# main_sheet.net
KiCad netlist of a schematic drawn in Altium Designer
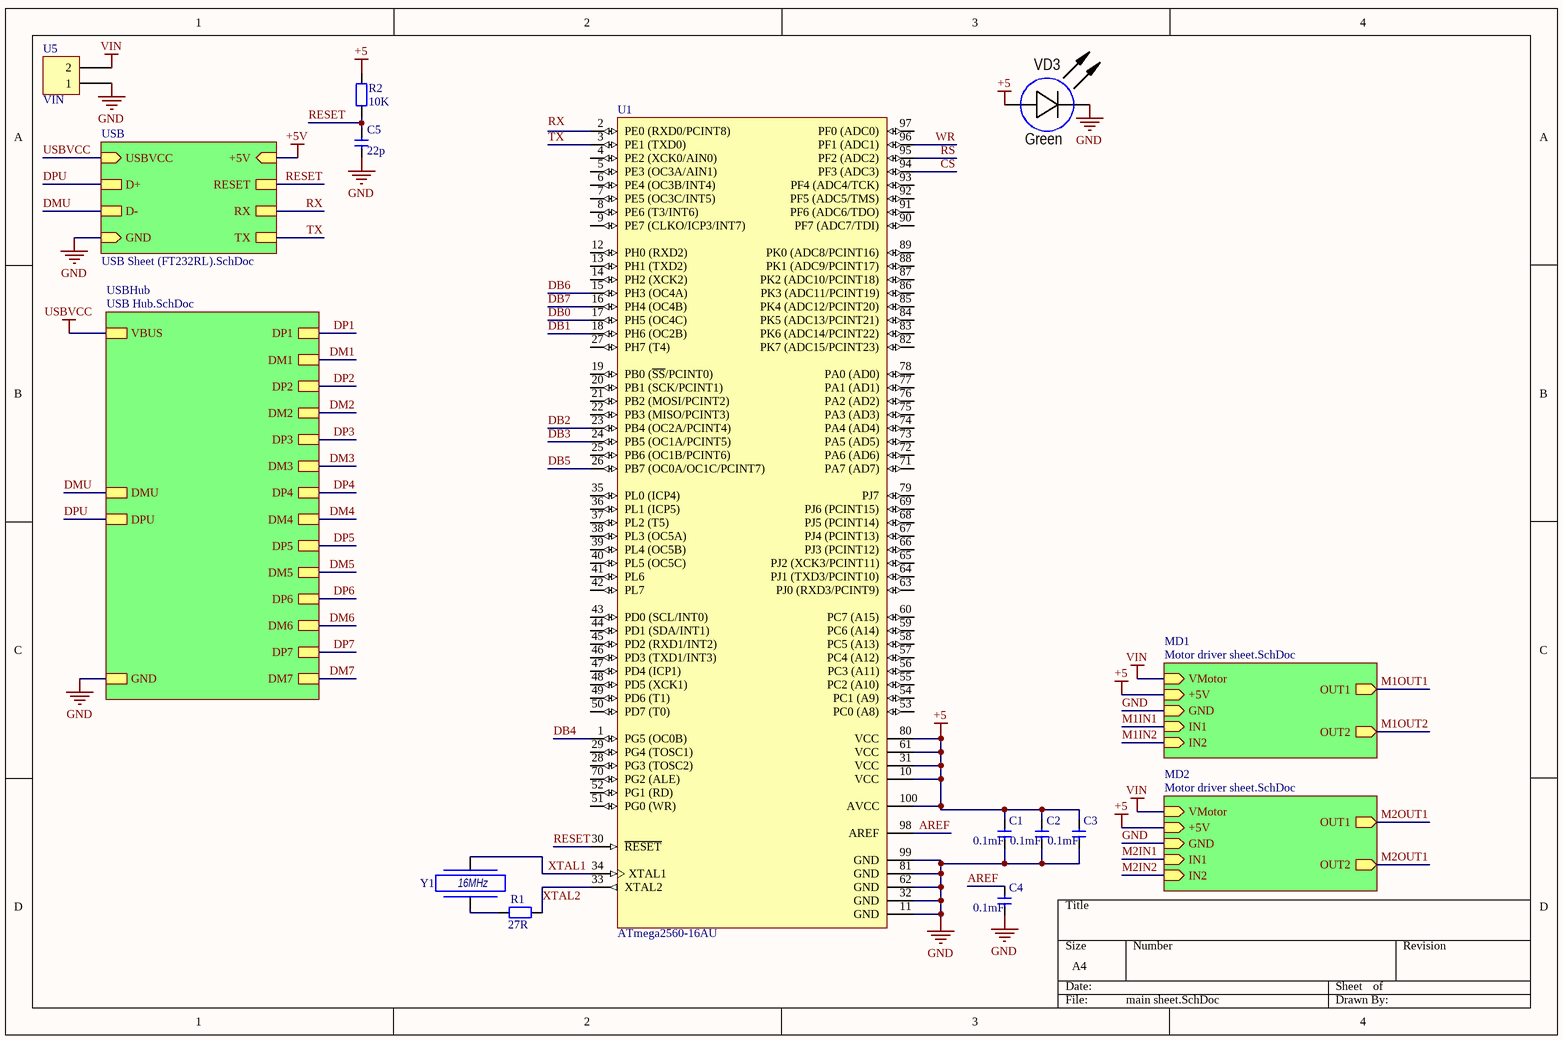
[diagram p0: main sheet.SchDoc]

(export (version "E")
  (design (tool "Eeschema 10.0.6"))
  (components
    (comp (ref "C1")
      (value "0.1mF")
      (footprint "cap0402")
      (libsource (lib "AlexChistiakov") (part "Cap SMD"))
    )
    (comp (ref "C2")
      (value "0.1mF")
      (footprint "cap0402")
      (libsource (lib "AlexChistiakov") (part "Cap SMD"))
    )
    (comp (ref "C3")
      (value "0.1mF")
      (footprint "cap0402")
      (libsource (lib "AlexChistiakov") (part "Cap SMD"))
    )
    (comp (ref "C4")
      (value "0.1mF")
      (footprint "cap0402")
      (libsource (lib "AlexChistiakov") (part "Cap SMD"))
    )
    (comp (ref "C5") (value "22p") (footprint "cap0603") (libsource (lib "AlexChistiakov") (part "Cap SMD")))
    (comp (ref "R1")
      (value "27R")
      (footprint "res0603")
      (libsource (lib "AlexChistiakov") (part "Resistor SMD"))
    )
    (comp (ref "R2")
      (value "10K")
      (footprint "res0603")
      (libsource (lib "AlexChistiakov") (part "Resistor SMD"))
    )
    (comp (ref "U1")
      (value "ATmega2560-16AU")
      (footprint "100A_N")
      (fields (field (name "PUBLISHER") "Altium Limited"))
      (libsource (lib "Atmel Microcontroller 8-Bit megaAVR") (part "ATmega2560-16AU"))
    )
    (comp (ref "U5")
      (value "VIN")
      (footprint "Power connectors")
      (libsource (lib "AlexChistiakov") (part "Power connectors"))
    )
    (comp (ref "VD3") (value "Green") (footprint "CH0603LB") (libsource (lib "Discrete") (part "LED")))
    (comp (ref "Y1")
      (value "16MHz")
      (footprint "QSMD5.0x3.2x1.0")
      (description "Кварцевый резонатор")
      (libsource (lib "TarabusLib_KOR") (part "Crystal"))
    )
  )
  (nets
    (net (code "1") (name "+5") (class "Default")
      (node (ref "C1") (pin "2") (pinfunction "2_2") (pintype "passive"))
      (node (ref "C2") (pin "2") (pinfunction "2_2") (pintype "passive"))
      (node (ref "C3") (pin "2") (pinfunction "2_2") (pintype "passive"))
      (node (ref "R2") (pin "2") (pinfunction "2_2") (pintype "passive"))
      (node (ref "U1") (pin "10") (pinfunction "VCC_10") (pintype "power_in"))
      (node (ref "U1") (pin "100") (pinfunction "AVCC_100") (pintype "power_in"))
      (node (ref "U1") (pin "31") (pinfunction "VCC_31") (pintype "power_in"))
      (node (ref "U1") (pin "61") (pinfunction "VCC_61") (pintype "power_in"))
      (node (ref "U1") (pin "80") (pinfunction "VCC_80") (pintype "power_in"))
      (node (ref "VD3") (pin "1") (pinfunction "A_1") (pintype "passive"))
    )
    (net (code "3") (name "/AREF") (class "Default")
      (node (ref "C4") (pin "2") (pinfunction "2_2") (pintype "passive"))
      (node (ref "U1") (pin "98") (pinfunction "AREF_98") (pintype "power_in"))
    )
    (net (code "4") (name "/CS") (class "Default")
      (node (ref "U1") (pin "94") (pinfunction "PF3_(ADC3)_94") (pintype "bidirectional"))
    )
    (net (code "5") (name "/DB0") (class "Default")
      (node (ref "U1") (pin "17") (pinfunction "PH5_(OC4C)_17") (pintype "bidirectional"))
    )
    (net (code "6") (name "/DB1") (class "Default")
      (node (ref "U1") (pin "18") (pinfunction "PH6_(OC2B)_18") (pintype "bidirectional"))
    )
    (net (code "7") (name "/DB2") (class "Default")
      (node (ref "U1") (pin "23") (pinfunction "PB4_(OC2A/PCINT4)_23") (pintype "bidirectional"))
    )
    (net (code "8") (name "/DB3") (class "Default")
      (node (ref "U1") (pin "24") (pinfunction "PB5_(OC1A/PCINT5)_24") (pintype "bidirectional"))
    )
    (net (code "9") (name "/DB4") (class "Default")
      (node (ref "U1") (pin "1") (pinfunction "PG5_(OC0B)_1") (pintype "bidirectional"))
    )
    (net (code "10") (name "/DB5") (class "Default")
      (node (ref "U1") (pin "26") (pinfunction "PB7_(OC0A/OC1C/PCINT7)_26") (pintype "bidirectional"))
    )
    (net (code "11") (name "/DB6") (class "Default")
      (node (ref "U1") (pin "15") (pinfunction "PH3_(OC4A)_15") (pintype "bidirectional"))
    )
    (net (code "12") (name "/DB7") (class "Default")
      (node (ref "U1") (pin "16") (pinfunction "PH4_(OC4B)_16") (pintype "bidirectional"))
    )
    (net (code "36") (name "/RESET") (class "Default")
      (node (ref "C5") (pin "2") (pinfunction "2_2") (pintype "passive"))
      (node (ref "R2") (pin "1") (pinfunction "1_1") (pintype "passive"))
      (node (ref "U1") (pin "30") (pinfunction "~{RESET}_30") (pintype "input"))
    )
    (net (code "37") (name "/RS") (class "Default")
      (node (ref "U1") (pin "95") (pinfunction "PF2_(ADC2)_95") (pintype "bidirectional"))
    )
    (net (code "39") (name "/TX") (class "Default")
      (node (ref "U1") (pin "3") (pinfunction "PE1_(TXD0)_3") (pintype "bidirectional"))
    )
    (net (code "40") (name "/WR") (class "Default")
      (node (ref "U1") (pin "96") (pinfunction "PF1_(ADC1)_96") (pintype "bidirectional"))
    )
    (net (code "41") (name "/XTAL1") (class "Default")
      (node (ref "U1") (pin "34") (pinfunction "XTAL1_34") (pintype "input"))
      (node (ref "Y1") (pin "2") (pinfunction "2_2") (pintype "passive"))
    )
    (net (code "42") (name "/XTAL2") (class "Default")
      (node (ref "R1") (pin "2") (pinfunction "2_2") (pintype "passive"))
      (node (ref "U1") (pin "33") (pinfunction "XTAL2_33") (pintype "output"))
    )
    (net (code "43") (name "GND") (class "Default")
      (node (ref "C1") (pin "1") (pinfunction "1_1") (pintype "passive"))
      (node (ref "C2") (pin "1") (pinfunction "1_1") (pintype "passive"))
      (node (ref "C3") (pin "1") (pinfunction "1_1") (pintype "passive"))
      (node (ref "C4") (pin "1") (pinfunction "1_1") (pintype "passive"))
      (node (ref "C5") (pin "1") (pinfunction "1_1") (pintype "passive"))
      (node (ref "U1") (pin "11") (pinfunction "GND_11") (pintype "power_in"))
      (node (ref "U1") (pin "32") (pinfunction "GND_32") (pintype "power_in"))
      (node (ref "U1") (pin "62") (pinfunction "GND_62") (pintype "power_in"))
      (node (ref "U1") (pin "81") (pinfunction "GND_81") (pintype "power_in"))
      (node (ref "U1") (pin "99") (pinfunction "GND_99") (pintype "power_in"))
      (node (ref "U5") (pin "1") (pinfunction "1_1") (pintype "power_in"))
      (node (ref "VD3") (pin "2") (pinfunction "C_2") (pintype "passive"))
    )
    (net (code "44") (name "Net-(R1-Pad1)") (class "Default")
      (node (ref "R1") (pin "1") (pinfunction "1_1") (pintype "passive"))
      (node (ref "Y1") (pin "1") (pinfunction "1_1") (pintype "passive"))
    )
    (net (code "46") (name "VIN") (class "Default")
      (node (ref "U5") (pin "2") (pinfunction "2_2") (pintype "power_in"))
    )
    (net (code "47") (name "unconnected-(U1-PA0_(AD0)-Pad78)") (class "Default")
      (node (ref "U1") (pin "78") (pinfunction "PA0_(AD0)_78") (pintype "bidirectional"))
    )
    (net (code "48") (name "unconnected-(U1-PA1_(AD1)-Pad77)") (class "Default")
      (node (ref "U1") (pin "77") (pinfunction "PA1_(AD1)_77") (pintype "bidirectional"))
    )
    (net (code "49") (name "unconnected-(U1-PA2_(AD2)-Pad76)") (class "Default")
      (node (ref "U1") (pin "76") (pinfunction "PA2_(AD2)_76") (pintype "bidirectional"))
    )
    (net (code "50") (name "unconnected-(U1-PA3_(AD3)-Pad75)") (class "Default")
      (node (ref "U1") (pin "75") (pinfunction "PA3_(AD3)_75") (pintype "bidirectional"))
    )
    (net (code "51") (name "unconnected-(U1-PA4_(AD4)-Pad74)") (class "Default")
      (node (ref "U1") (pin "74") (pinfunction "PA4_(AD4)_74") (pintype "bidirectional"))
    )
    (net (code "52") (name "unconnected-(U1-PA5_(AD5)-Pad73)") (class "Default")
      (node (ref "U1") (pin "73") (pinfunction "PA5_(AD5)_73") (pintype "bidirectional"))
    )
    (net (code "53") (name "unconnected-(U1-PA6_(AD6)-Pad72)") (class "Default")
      (node (ref "U1") (pin "72") (pinfunction "PA6_(AD6)_72") (pintype "bidirectional"))
    )
    (net (code "54") (name "unconnected-(U1-PA7_(AD7)-Pad71)") (class "Default")
      (node (ref "U1") (pin "71") (pinfunction "PA7_(AD7)_71") (pintype "bidirectional"))
    )
    (net (code "55") (name "unconnected-(U1-PB0_(~{SS}{slash}PCINT0)-Pad19)") (class "Default")
      (node (ref "U1") (pin "19") (pinfunction "PB0_(~{SS}/PCINT0)_19") (pintype "bidirectional"))
    )
    (net (code "56") (name "unconnected-(U1-PB1_(SCK{slash}PCINT1)-Pad20)") (class "Default")
      (node (ref "U1") (pin "20") (pinfunction "PB1_(SCK/PCINT1)_20") (pintype "bidirectional"))
    )
    (net (code "57") (name "unconnected-(U1-PB2_(MOSI{slash}PCINT2)-Pad21)") (class "Default")
      (node (ref "U1") (pin "21") (pinfunction "PB2_(MOSI/PCINT2)_21") (pintype "bidirectional"))
    )
    (net (code "58") (name "unconnected-(U1-PB3_(MISO{slash}PCINT3)-Pad22)") (class "Default")
      (node (ref "U1") (pin "22") (pinfunction "PB3_(MISO/PCINT3)_22") (pintype "bidirectional"))
    )
    (net (code "59") (name "unconnected-(U1-PB6_(OC1B{slash}PCINT6)-Pad25)") (class "Default")
      (node (ref "U1") (pin "25") (pinfunction "PB6_(OC1B/PCINT6)_25") (pintype "bidirectional"))
    )
    (net (code "60") (name "unconnected-(U1-PC0_(A8)-Pad53)") (class "Default")
      (node (ref "U1") (pin "53") (pinfunction "PC0_(A8)_53") (pintype "bidirectional"))
    )
    (net (code "61") (name "unconnected-(U1-PC1_(A9)-Pad54)") (class "Default")
      (node (ref "U1") (pin "54") (pinfunction "PC1_(A9)_54") (pintype "bidirectional"))
    )
    (net (code "62") (name "unconnected-(U1-PC2_(A10)-Pad55)") (class "Default")
      (node (ref "U1") (pin "55") (pinfunction "PC2_(A10)_55") (pintype "bidirectional"))
    )
    (net (code "63") (name "unconnected-(U1-PC3_(A11)-Pad56)") (class "Default")
      (node (ref "U1") (pin "56") (pinfunction "PC3_(A11)_56") (pintype "bidirectional"))
    )
    (net (code "64") (name "unconnected-(U1-PC4_(A12)-Pad57)") (class "Default")
      (node (ref "U1") (pin "57") (pinfunction "PC4_(A12)_57") (pintype "bidirectional"))
    )
    (net (code "65") (name "unconnected-(U1-PC5_(A13)-Pad58)") (class "Default")
      (node (ref "U1") (pin "58") (pinfunction "PC5_(A13)_58") (pintype "bidirectional"))
    )
    (net (code "66") (name "unconnected-(U1-PC6_(A14)-Pad59)") (class "Default")
      (node (ref "U1") (pin "59") (pinfunction "PC6_(A14)_59") (pintype "bidirectional"))
    )
    (net (code "67") (name "unconnected-(U1-PC7_(A15)-Pad60)") (class "Default")
      (node (ref "U1") (pin "60") (pinfunction "PC7_(A15)_60") (pintype "bidirectional"))
    )
    (net (code "68") (name "unconnected-(U1-PD0_(SCL{slash}INT0)-Pad43)") (class "Default")
      (node (ref "U1") (pin "43") (pinfunction "PD0_(SCL/INT0)_43") (pintype "bidirectional"))
    )
    (net (code "69") (name "unconnected-(U1-PD1_(SDA{slash}INT1)-Pad44)") (class "Default")
      (node (ref "U1") (pin "44") (pinfunction "PD1_(SDA/INT1)_44") (pintype "bidirectional"))
    )
    (net (code "70") (name "unconnected-(U1-PD2_(RXD1{slash}INT2)-Pad45)") (class "Default")
      (node (ref "U1") (pin "45") (pinfunction "PD2_(RXD1/INT2)_45") (pintype "bidirectional"))
    )
    (net (code "71") (name "unconnected-(U1-PD3_(TXD1{slash}INT3)-Pad46)") (class "Default")
      (node (ref "U1") (pin "46") (pinfunction "PD3_(TXD1/INT3)_46") (pintype "bidirectional"))
    )
    (net (code "72") (name "unconnected-(U1-PD4_(ICP1)-Pad47)") (class "Default")
      (node (ref "U1") (pin "47") (pinfunction "PD4_(ICP1)_47") (pintype "bidirectional"))
    )
    (net (code "73") (name "unconnected-(U1-PD5_(XCK1)-Pad48)") (class "Default")
      (node (ref "U1") (pin "48") (pinfunction "PD5_(XCK1)_48") (pintype "bidirectional"))
    )
    (net (code "74") (name "unconnected-(U1-PD6_(T1)-Pad49)") (class "Default")
      (node (ref "U1") (pin "49") (pinfunction "PD6_(T1)_49") (pintype "bidirectional"))
    )
    (net (code "75") (name "unconnected-(U1-PD7_(T0)-Pad50)") (class "Default")
      (node (ref "U1") (pin "50") (pinfunction "PD7_(T0)_50") (pintype "bidirectional"))
    )
    (net (code "76") (name "unconnected-(U1-PE0_(RXD0{slash}PCINT8)-Pad2)") (class "Default")
      (node (ref "U1") (pin "2") (pinfunction "PE0_(RXD0/PCINT8)_2") (pintype "bidirectional"))
    )
    (net (code "77") (name "unconnected-(U1-PE2_(XCK0{slash}AIN0)-Pad4)") (class "Default")
      (node (ref "U1") (pin "4") (pinfunction "PE2_(XCK0/AIN0)_4") (pintype "bidirectional"))
    )
    (net (code "78") (name "unconnected-(U1-PE3_(OC3A{slash}AIN1)-Pad5)") (class "Default")
      (node (ref "U1") (pin "5") (pinfunction "PE3_(OC3A/AIN1)_5") (pintype "bidirectional"))
    )
    (net (code "79") (name "unconnected-(U1-PE4_(OC3B{slash}INT4)-Pad6)") (class "Default")
      (node (ref "U1") (pin "6") (pinfunction "PE4_(OC3B/INT4)_6") (pintype "bidirectional"))
    )
    (net (code "80") (name "unconnected-(U1-PE5_(OC3C{slash}INT5)-Pad7)") (class "Default")
      (node (ref "U1") (pin "7") (pinfunction "PE5_(OC3C/INT5)_7") (pintype "bidirectional"))
    )
    (net (code "81") (name "unconnected-(U1-PE6_(T3{slash}INT6)-Pad8)") (class "Default")
      (node (ref "U1") (pin "8") (pinfunction "PE6_(T3/INT6)_8") (pintype "bidirectional"))
    )
    (net (code "82") (name "unconnected-(U1-PE7_(CLKO{slash}ICP3{slash}INT7)-Pad9)") (class "Default")
      (node (ref "U1") (pin "9") (pinfunction "PE7_(CLKO/ICP3/INT7)_9") (pintype "bidirectional"))
    )
    (net (code "83") (name "unconnected-(U1-PF0_(ADC0)-Pad97)") (class "Default")
      (node (ref "U1") (pin "97") (pinfunction "PF0_(ADC0)_97") (pintype "bidirectional"))
    )
    (net (code "84") (name "unconnected-(U1-PF4_(ADC4{slash}TCK)-Pad93)") (class "Default")
      (node (ref "U1") (pin "93") (pinfunction "PF4_(ADC4/TCK)_93") (pintype "bidirectional"))
    )
    (net (code "85") (name "unconnected-(U1-PF5_(ADC5{slash}TMS)-Pad92)") (class "Default")
      (node (ref "U1") (pin "92") (pinfunction "PF5_(ADC5/TMS)_92") (pintype "bidirectional"))
    )
    (net (code "86") (name "unconnected-(U1-PF6_(ADC6{slash}TDO)-Pad91)") (class "Default")
      (node (ref "U1") (pin "91") (pinfunction "PF6_(ADC6/TDO)_91") (pintype "bidirectional"))
    )
    (net (code "87") (name "unconnected-(U1-PF7_(ADC7{slash}TDI)-Pad90)") (class "Default")
      (node (ref "U1") (pin "90") (pinfunction "PF7_(ADC7/TDI)_90") (pintype "bidirectional"))
    )
    (net (code "88") (name "unconnected-(U1-PG0_(WR)-Pad51)") (class "Default")
      (node (ref "U1") (pin "51") (pinfunction "PG0_(WR)_51") (pintype "bidirectional"))
    )
    (net (code "89") (name "unconnected-(U1-PG1_(RD)-Pad52)") (class "Default")
      (node (ref "U1") (pin "52") (pinfunction "PG1_(RD)_52") (pintype "bidirectional"))
    )
    (net (code "90") (name "unconnected-(U1-PG2_(ALE)-Pad70)") (class "Default")
      (node (ref "U1") (pin "70") (pinfunction "PG2_(ALE)_70") (pintype "bidirectional"))
    )
    (net (code "91") (name "unconnected-(U1-PG3_(TOSC2)-Pad28)") (class "Default")
      (node (ref "U1") (pin "28") (pinfunction "PG3_(TOSC2)_28") (pintype "bidirectional"))
    )
    (net (code "92") (name "unconnected-(U1-PG4_(TOSC1)-Pad29)") (class "Default")
      (node (ref "U1") (pin "29") (pinfunction "PG4_(TOSC1)_29") (pintype "bidirectional"))
    )
    (net (code "93") (name "unconnected-(U1-PH0_(RXD2)-Pad12)") (class "Default")
      (node (ref "U1") (pin "12") (pinfunction "PH0_(RXD2)_12") (pintype "bidirectional"))
    )
    (net (code "94") (name "unconnected-(U1-PH1_(TXD2)-Pad13)") (class "Default")
      (node (ref "U1") (pin "13") (pinfunction "PH1_(TXD2)_13") (pintype "bidirectional"))
    )
    (net (code "95") (name "unconnected-(U1-PH2_(XCK2)-Pad14)") (class "Default")
      (node (ref "U1") (pin "14") (pinfunction "PH2_(XCK2)_14") (pintype "bidirectional"))
    )
    (net (code "96") (name "unconnected-(U1-PH7_(T4)-Pad27)") (class "Default")
      (node (ref "U1") (pin "27") (pinfunction "PH7_(T4)_27") (pintype "bidirectional"))
    )
    (net (code "97") (name "unconnected-(U1-PJ0_(RXD3{slash}PCINT9)-Pad63)") (class "Default")
      (node (ref "U1") (pin "63") (pinfunction "PJ0_(RXD3/PCINT9)_63") (pintype "bidirectional"))
    )
    (net (code "98") (name "unconnected-(U1-PJ1_(TXD3{slash}PCINT10)-Pad64)") (class "Default")
      (node (ref "U1") (pin "64") (pinfunction "PJ1_(TXD3/PCINT10)_64") (pintype "bidirectional"))
    )
    (net (code "99") (name "unconnected-(U1-PJ2_(XCK3{slash}PCINT11)-Pad65)") (class "Default")
      (node (ref "U1") (pin "65") (pinfunction "PJ2_(XCK3/PCINT11)_65") (pintype "bidirectional"))
    )
    (net (code "100") (name "unconnected-(U1-PJ3_(PCINT12)-Pad66)") (class "Default")
      (node (ref "U1") (pin "66") (pinfunction "PJ3_(PCINT12)_66") (pintype "bidirectional"))
    )
    (net (code "101") (name "unconnected-(U1-PJ4_(PCINT13)-Pad67)") (class "Default")
      (node (ref "U1") (pin "67") (pinfunction "PJ4_(PCINT13)_67") (pintype "bidirectional"))
    )
    (net (code "102") (name "unconnected-(U1-PJ5_(PCINT14)-Pad68)") (class "Default")
      (node (ref "U1") (pin "68") (pinfunction "PJ5_(PCINT14)_68") (pintype "bidirectional"))
    )
    (net (code "103") (name "unconnected-(U1-PJ6_(PCINT15)-Pad69)") (class "Default")
      (node (ref "U1") (pin "69") (pinfunction "PJ6_(PCINT15)_69") (pintype "bidirectional"))
    )
    (net (code "104") (name "unconnected-(U1-PJ7-Pad79)") (class "Default")
      (node (ref "U1") (pin "79") (pinfunction "PJ7_79") (pintype "bidirectional"))
    )
    (net (code "105") (name "unconnected-(U1-PK0_(ADC8{slash}PCINT16)-Pad89)") (class "Default")
      (node (ref "U1") (pin "89") (pinfunction "PK0_(ADC8/PCINT16)_89") (pintype "bidirectional"))
    )
    (net (code "106") (name "unconnected-(U1-PK1_(ADC9{slash}PCINT17)-Pad88)") (class "Default")
      (node (ref "U1") (pin "88") (pinfunction "PK1_(ADC9/PCINT17)_88") (pintype "bidirectional"))
    )
    (net (code "107") (name "unconnected-(U1-PK2_(ADC10{slash}PCINT18)-Pad87)") (class "Default")
      (node (ref "U1") (pin "87") (pinfunction "PK2_(ADC10/PCINT18)_87") (pintype "bidirectional"))
    )
    (net (code "108") (name "unconnected-(U1-PK3_(ADC11{slash}PCINT19)-Pad86)") (class "Default")
      (node (ref "U1") (pin "86") (pinfunction "PK3_(ADC11/PCINT19)_86") (pintype "bidirectional"))
    )
    (net (code "109") (name "unconnected-(U1-PK4_(ADC12{slash}PCINT20)-Pad85)") (class "Default")
      (node (ref "U1") (pin "85") (pinfunction "PK4_(ADC12/PCINT20)_85") (pintype "bidirectional"))
    )
    (net (code "110") (name "unconnected-(U1-PK5_(ADC13{slash}PCINT21)-Pad84)") (class "Default")
      (node (ref "U1") (pin "84") (pinfunction "PK5_(ADC13/PCINT21)_84") (pintype "bidirectional"))
    )
    (net (code "111") (name "unconnected-(U1-PK6_(ADC14{slash}PCINT22)-Pad83)") (class "Default")
      (node (ref "U1") (pin "83") (pinfunction "PK6_(ADC14/PCINT22)_83") (pintype "bidirectional"))
    )
    (net (code "112") (name "unconnected-(U1-PK7_(ADC15{slash}PCINT23)-Pad82)") (class "Default")
      (node (ref "U1") (pin "82") (pinfunction "PK7_(ADC15/PCINT23)_82") (pintype "bidirectional"))
    )
    (net (code "113") (name "unconnected-(U1-PL0_(ICP4)-Pad35)") (class "Default")
      (node (ref "U1") (pin "35") (pinfunction "PL0_(ICP4)_35") (pintype "bidirectional"))
    )
    (net (code "114") (name "unconnected-(U1-PL1_(ICP5)-Pad36)") (class "Default")
      (node (ref "U1") (pin "36") (pinfunction "PL1_(ICP5)_36") (pintype "bidirectional"))
    )
    (net (code "115") (name "unconnected-(U1-PL2_(T5)-Pad37)") (class "Default")
      (node (ref "U1") (pin "37") (pinfunction "PL2_(T5)_37") (pintype "bidirectional"))
    )
    (net (code "116") (name "unconnected-(U1-PL3_(OC5A)-Pad38)") (class "Default")
      (node (ref "U1") (pin "38") (pinfunction "PL3_(OC5A)_38") (pintype "bidirectional"))
    )
    (net (code "117") (name "unconnected-(U1-PL4_(OC5B)-Pad39)") (class "Default")
      (node (ref "U1") (pin "39") (pinfunction "PL4_(OC5B)_39") (pintype "bidirectional"))
    )
    (net (code "118") (name "unconnected-(U1-PL5_(OC5C)-Pad40)") (class "Default")
      (node (ref "U1") (pin "40") (pinfunction "PL5_(OC5C)_40") (pintype "bidirectional"))
    )
    (net (code "119") (name "unconnected-(U1-PL6-Pad41)") (class "Default")
      (node (ref "U1") (pin "41") (pinfunction "PL6_41") (pintype "bidirectional"))
    )
    (net (code "120") (name "unconnected-(U1-PL7-Pad42)") (class "Default")
      (node (ref "U1") (pin "42") (pinfunction "PL7_42") (pintype "bidirectional"))
    )
  )
)
